# EIB-128v2.net
KiCad netlist of a schematic drawn in EAGLE
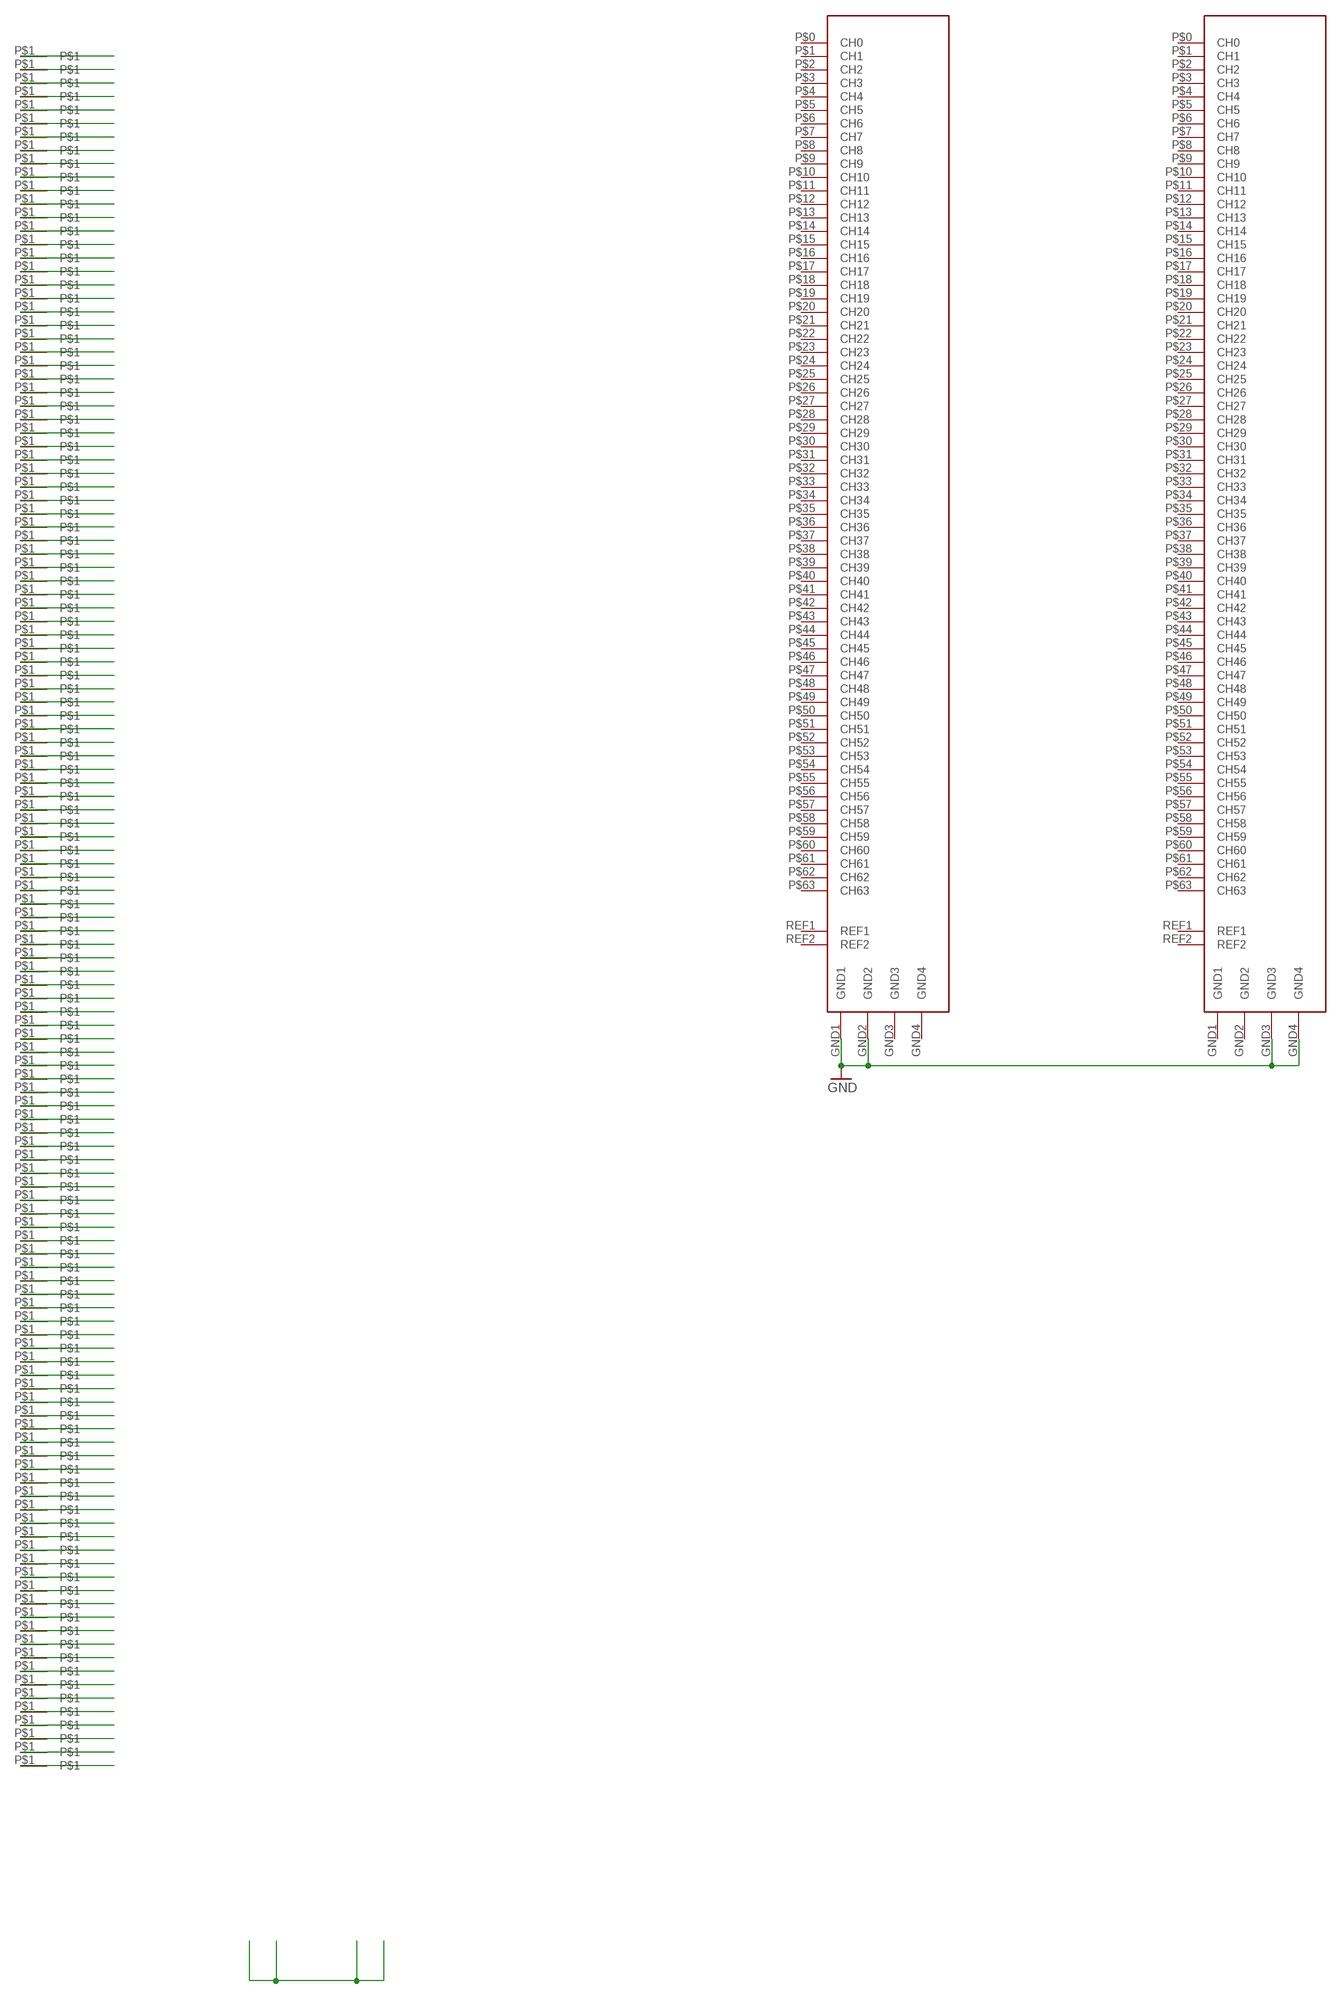
[diagram p0: schematic, sheet 1]

(export (version "E")
  (design (tool "Eeschema 10.0.6"))
  (components
    (comp (ref "H$0")
      (value "TARRAYSHUTTLEHOLE")
      (footprint "eagle-import:TARRAYSHUTTLEHOLE")
      (libsource (lib "eagle-import") (part "TARRAYSHUTTLEHOLE"))
    )
    (comp (ref "H$1")
      (value "TARRAYSHUTTLEHOLE")
      (footprint "eagle-import:TARRAYSHUTTLEHOLE")
      (libsource (lib "eagle-import") (part "TARRAYSHUTTLEHOLE"))
    )
    (comp (ref "H$2")
      (value "TARRAYSHUTTLEHOLE")
      (footprint "eagle-import:TARRAYSHUTTLEHOLE")
      (libsource (lib "eagle-import") (part "TARRAYSHUTTLEHOLE"))
    )
    (comp (ref "H$3")
      (value "TARRAYSHUTTLEHOLE")
      (footprint "eagle-import:TARRAYSHUTTLEHOLE")
      (libsource (lib "eagle-import") (part "TARRAYSHUTTLEHOLE"))
    )
    (comp (ref "H$4")
      (value "TARRAYSHUTTLEHOLE")
      (footprint "eagle-import:TARRAYSHUTTLEHOLE")
      (libsource (lib "eagle-import") (part "TARRAYSHUTTLEHOLE"))
    )
    (comp (ref "H$5")
      (value "TARRAYSHUTTLEHOLE")
      (footprint "eagle-import:TARRAYSHUTTLEHOLE")
      (libsource (lib "eagle-import") (part "TARRAYSHUTTLEHOLE"))
    )
    (comp (ref "H$6")
      (value "TARRAYSHUTTLEHOLE")
      (footprint "eagle-import:TARRAYSHUTTLEHOLE")
      (libsource (lib "eagle-import") (part "TARRAYSHUTTLEHOLE"))
    )
    (comp (ref "H$7")
      (value "TARRAYSHUTTLEHOLE")
      (footprint "eagle-import:TARRAYSHUTTLEHOLE")
      (libsource (lib "eagle-import") (part "TARRAYSHUTTLEHOLE"))
    )
    (comp (ref "H$8")
      (value "TARRAYSHUTTLEHOLE")
      (footprint "eagle-import:TARRAYSHUTTLEHOLE")
      (libsource (lib "eagle-import") (part "TARRAYSHUTTLEHOLE"))
    )
    (comp (ref "H$9")
      (value "TARRAYSHUTTLEHOLE")
      (footprint "eagle-import:TARRAYSHUTTLEHOLE")
      (libsource (lib "eagle-import") (part "TARRAYSHUTTLEHOLE"))
    )
    (comp (ref "H$10")
      (value "TARRAYSHUTTLEHOLE")
      (footprint "eagle-import:TARRAYSHUTTLEHOLE")
      (libsource (lib "eagle-import") (part "TARRAYSHUTTLEHOLE"))
    )
    (comp (ref "H$11")
      (value "TARRAYSHUTTLEHOLE")
      (footprint "eagle-import:TARRAYSHUTTLEHOLE")
      (libsource (lib "eagle-import") (part "TARRAYSHUTTLEHOLE"))
    )
    (comp (ref "H$12")
      (value "TARRAYSHUTTLEHOLE")
      (footprint "eagle-import:TARRAYSHUTTLEHOLE")
      (libsource (lib "eagle-import") (part "TARRAYSHUTTLEHOLE"))
    )
    (comp (ref "H$13")
      (value "TARRAYSHUTTLEHOLE")
      (footprint "eagle-import:TARRAYSHUTTLEHOLE")
      (libsource (lib "eagle-import") (part "TARRAYSHUTTLEHOLE"))
    )
    (comp (ref "H$14")
      (value "TARRAYSHUTTLEHOLE")
      (footprint "eagle-import:TARRAYSHUTTLEHOLE")
      (libsource (lib "eagle-import") (part "TARRAYSHUTTLEHOLE"))
    )
    (comp (ref "H$15")
      (value "TARRAYSHUTTLEHOLE")
      (footprint "eagle-import:TARRAYSHUTTLEHOLE")
      (libsource (lib "eagle-import") (part "TARRAYSHUTTLEHOLE"))
    )
    (comp (ref "H$16")
      (value "TARRAYSHUTTLEHOLE")
      (footprint "eagle-import:TARRAYSHUTTLEHOLE")
      (libsource (lib "eagle-import") (part "TARRAYSHUTTLEHOLE"))
    )
    (comp (ref "H$17")
      (value "TARRAYSHUTTLEHOLE")
      (footprint "eagle-import:TARRAYSHUTTLEHOLE")
      (libsource (lib "eagle-import") (part "TARRAYSHUTTLEHOLE"))
    )
    (comp (ref "H$18")
      (value "TARRAYSHUTTLEHOLE")
      (footprint "eagle-import:TARRAYSHUTTLEHOLE")
      (libsource (lib "eagle-import") (part "TARRAYSHUTTLEHOLE"))
    )
    (comp (ref "H$19")
      (value "TARRAYSHUTTLEHOLE")
      (footprint "eagle-import:TARRAYSHUTTLEHOLE")
      (libsource (lib "eagle-import") (part "TARRAYSHUTTLEHOLE"))
    )
    (comp (ref "H$20")
      (value "TARRAYSHUTTLEHOLE")
      (footprint "eagle-import:TARRAYSHUTTLEHOLE")
      (libsource (lib "eagle-import") (part "TARRAYSHUTTLEHOLE"))
    )
    (comp (ref "H$21")
      (value "TARRAYSHUTTLEHOLE")
      (footprint "eagle-import:TARRAYSHUTTLEHOLE")
      (libsource (lib "eagle-import") (part "TARRAYSHUTTLEHOLE"))
    )
    (comp (ref "H$22")
      (value "TARRAYSHUTTLEHOLE")
      (footprint "eagle-import:TARRAYSHUTTLEHOLE")
      (libsource (lib "eagle-import") (part "TARRAYSHUTTLEHOLE"))
    )
    (comp (ref "H$23")
      (value "TARRAYSHUTTLEHOLE")
      (footprint "eagle-import:TARRAYSHUTTLEHOLE")
      (libsource (lib "eagle-import") (part "TARRAYSHUTTLEHOLE"))
    )
    (comp (ref "H$24")
      (value "TARRAYSHUTTLEHOLE")
      (footprint "eagle-import:TARRAYSHUTTLEHOLE")
      (libsource (lib "eagle-import") (part "TARRAYSHUTTLEHOLE"))
    )
    (comp (ref "H$25")
      (value "TARRAYSHUTTLEHOLE")
      (footprint "eagle-import:TARRAYSHUTTLEHOLE")
      (libsource (lib "eagle-import") (part "TARRAYSHUTTLEHOLE"))
    )
    (comp (ref "H$26")
      (value "TARRAYSHUTTLEHOLE")
      (footprint "eagle-import:TARRAYSHUTTLEHOLE")
      (libsource (lib "eagle-import") (part "TARRAYSHUTTLEHOLE"))
    )
    (comp (ref "H$27")
      (value "TARRAYSHUTTLEHOLE")
      (footprint "eagle-import:TARRAYSHUTTLEHOLE")
      (libsource (lib "eagle-import") (part "TARRAYSHUTTLEHOLE"))
    )
    (comp (ref "H$28")
      (value "TARRAYSHUTTLEHOLE")
      (footprint "eagle-import:TARRAYSHUTTLEHOLE")
      (libsource (lib "eagle-import") (part "TARRAYSHUTTLEHOLE"))
    )
    (comp (ref "H$29")
      (value "TARRAYSHUTTLEHOLE")
      (footprint "eagle-import:TARRAYSHUTTLEHOLE")
      (libsource (lib "eagle-import") (part "TARRAYSHUTTLEHOLE"))
    )
    (comp (ref "H$30")
      (value "TARRAYSHUTTLEHOLE")
      (footprint "eagle-import:TARRAYSHUTTLEHOLE")
      (libsource (lib "eagle-import") (part "TARRAYSHUTTLEHOLE"))
    )
    (comp (ref "H$31")
      (value "TARRAYSHUTTLEHOLE")
      (footprint "eagle-import:TARRAYSHUTTLEHOLE")
      (libsource (lib "eagle-import") (part "TARRAYSHUTTLEHOLE"))
    )
    (comp (ref "H$32")
      (value "TARRAYSHUTTLEHOLE")
      (footprint "eagle-import:TARRAYSHUTTLEHOLE")
      (libsource (lib "eagle-import") (part "TARRAYSHUTTLEHOLE"))
    )
    (comp (ref "H$33")
      (value "TARRAYSHUTTLEHOLE")
      (footprint "eagle-import:TARRAYSHUTTLEHOLE")
      (libsource (lib "eagle-import") (part "TARRAYSHUTTLEHOLE"))
    )
    (comp (ref "H$34")
      (value "TARRAYSHUTTLEHOLE")
      (footprint "eagle-import:TARRAYSHUTTLEHOLE")
      (libsource (lib "eagle-import") (part "TARRAYSHUTTLEHOLE"))
    )
    (comp (ref "H$35")
      (value "TARRAYSHUTTLEHOLE")
      (footprint "eagle-import:TARRAYSHUTTLEHOLE")
      (libsource (lib "eagle-import") (part "TARRAYSHUTTLEHOLE"))
    )
    (comp (ref "H$36")
      (value "TARRAYSHUTTLEHOLE")
      (footprint "eagle-import:TARRAYSHUTTLEHOLE")
      (libsource (lib "eagle-import") (part "TARRAYSHUTTLEHOLE"))
    )
    (comp (ref "H$37")
      (value "TARRAYSHUTTLEHOLE")
      (footprint "eagle-import:TARRAYSHUTTLEHOLE")
      (libsource (lib "eagle-import") (part "TARRAYSHUTTLEHOLE"))
    )
    (comp (ref "H$38")
      (value "TARRAYSHUTTLEHOLE")
      (footprint "eagle-import:TARRAYSHUTTLEHOLE")
      (libsource (lib "eagle-import") (part "TARRAYSHUTTLEHOLE"))
    )
    (comp (ref "H$39")
      (value "TARRAYSHUTTLEHOLE")
      (footprint "eagle-import:TARRAYSHUTTLEHOLE")
      (libsource (lib "eagle-import") (part "TARRAYSHUTTLEHOLE"))
    )
    (comp (ref "H$40")
      (value "TARRAYSHUTTLEHOLE")
      (footprint "eagle-import:TARRAYSHUTTLEHOLE")
      (libsource (lib "eagle-import") (part "TARRAYSHUTTLEHOLE"))
    )
    (comp (ref "H$41")
      (value "TARRAYSHUTTLEHOLE")
      (footprint "eagle-import:TARRAYSHUTTLEHOLE")
      (libsource (lib "eagle-import") (part "TARRAYSHUTTLEHOLE"))
    )
    (comp (ref "H$42")
      (value "TARRAYSHUTTLEHOLE")
      (footprint "eagle-import:TARRAYSHUTTLEHOLE")
      (libsource (lib "eagle-import") (part "TARRAYSHUTTLEHOLE"))
    )
    (comp (ref "H$43")
      (value "TARRAYSHUTTLEHOLE")
      (footprint "eagle-import:TARRAYSHUTTLEHOLE")
      (libsource (lib "eagle-import") (part "TARRAYSHUTTLEHOLE"))
    )
    (comp (ref "H$44")
      (value "TARRAYSHUTTLEHOLE")
      (footprint "eagle-import:TARRAYSHUTTLEHOLE")
      (libsource (lib "eagle-import") (part "TARRAYSHUTTLEHOLE"))
    )
    (comp (ref "H$45")
      (value "TARRAYSHUTTLEHOLE")
      (footprint "eagle-import:TARRAYSHUTTLEHOLE")
      (libsource (lib "eagle-import") (part "TARRAYSHUTTLEHOLE"))
    )
    (comp (ref "H$46")
      (value "TARRAYSHUTTLEHOLE")
      (footprint "eagle-import:TARRAYSHUTTLEHOLE")
      (libsource (lib "eagle-import") (part "TARRAYSHUTTLEHOLE"))
    )
    (comp (ref "H$47")
      (value "TARRAYSHUTTLEHOLE")
      (footprint "eagle-import:TARRAYSHUTTLEHOLE")
      (libsource (lib "eagle-import") (part "TARRAYSHUTTLEHOLE"))
    )
    (comp (ref "H$48")
      (value "TARRAYSHUTTLEHOLE")
      (footprint "eagle-import:TARRAYSHUTTLEHOLE")
      (libsource (lib "eagle-import") (part "TARRAYSHUTTLEHOLE"))
    )
    (comp (ref "H$49")
      (value "TARRAYSHUTTLEHOLE")
      (footprint "eagle-import:TARRAYSHUTTLEHOLE")
      (libsource (lib "eagle-import") (part "TARRAYSHUTTLEHOLE"))
    )
    (comp (ref "H$50")
      (value "TARRAYSHUTTLEHOLE")
      (footprint "eagle-import:TARRAYSHUTTLEHOLE")
      (libsource (lib "eagle-import") (part "TARRAYSHUTTLEHOLE"))
    )
    (comp (ref "H$51")
      (value "TARRAYSHUTTLEHOLE")
      (footprint "eagle-import:TARRAYSHUTTLEHOLE")
      (libsource (lib "eagle-import") (part "TARRAYSHUTTLEHOLE"))
    )
    (comp (ref "H$52")
      (value "TARRAYSHUTTLEHOLE")
      (footprint "eagle-import:TARRAYSHUTTLEHOLE")
      (libsource (lib "eagle-import") (part "TARRAYSHUTTLEHOLE"))
    )
    (comp (ref "H$53")
      (value "TARRAYSHUTTLEHOLE")
      (footprint "eagle-import:TARRAYSHUTTLEHOLE")
      (libsource (lib "eagle-import") (part "TARRAYSHUTTLEHOLE"))
    )
    (comp (ref "H$54")
      (value "TARRAYSHUTTLEHOLE")
      (footprint "eagle-import:TARRAYSHUTTLEHOLE")
      (libsource (lib "eagle-import") (part "TARRAYSHUTTLEHOLE"))
    )
    (comp (ref "H$55")
      (value "TARRAYSHUTTLEHOLE")
      (footprint "eagle-import:TARRAYSHUTTLEHOLE")
      (libsource (lib "eagle-import") (part "TARRAYSHUTTLEHOLE"))
    )
    (comp (ref "H$56")
      (value "TARRAYSHUTTLEHOLE")
      (footprint "eagle-import:TARRAYSHUTTLEHOLE")
      (libsource (lib "eagle-import") (part "TARRAYSHUTTLEHOLE"))
    )
    (comp (ref "H$57")
      (value "TARRAYSHUTTLEHOLE")
      (footprint "eagle-import:TARRAYSHUTTLEHOLE")
      (libsource (lib "eagle-import") (part "TARRAYSHUTTLEHOLE"))
    )
    (comp (ref "H$58")
      (value "TARRAYSHUTTLEHOLE")
      (footprint "eagle-import:TARRAYSHUTTLEHOLE")
      (libsource (lib "eagle-import") (part "TARRAYSHUTTLEHOLE"))
    )
    (comp (ref "H$59")
      (value "TARRAYSHUTTLEHOLE")
      (footprint "eagle-import:TARRAYSHUTTLEHOLE")
      (libsource (lib "eagle-import") (part "TARRAYSHUTTLEHOLE"))
    )
    (comp (ref "H$60")
      (value "TARRAYSHUTTLEHOLE")
      (footprint "eagle-import:TARRAYSHUTTLEHOLE")
      (libsource (lib "eagle-import") (part "TARRAYSHUTTLEHOLE"))
    )
    (comp (ref "H$61")
      (value "TARRAYSHUTTLEHOLE")
      (footprint "eagle-import:TARRAYSHUTTLEHOLE")
      (libsource (lib "eagle-import") (part "TARRAYSHUTTLEHOLE"))
    )
    (comp (ref "H$62")
      (value "TARRAYSHUTTLEHOLE")
      (footprint "eagle-import:TARRAYSHUTTLEHOLE")
      (libsource (lib "eagle-import") (part "TARRAYSHUTTLEHOLE"))
    )
    (comp (ref "H$63")
      (value "TARRAYSHUTTLEHOLE")
      (footprint "eagle-import:TARRAYSHUTTLEHOLE")
      (libsource (lib "eagle-import") (part "TARRAYSHUTTLEHOLE"))
    )
    (comp (ref "H$64")
      (value "TARRAYSHUTTLEHOLE")
      (footprint "eagle-import:TARRAYSHUTTLEHOLE")
      (libsource (lib "eagle-import") (part "TARRAYSHUTTLEHOLE"))
    )
    (comp (ref "H$65")
      (value "TARRAYSHUTTLEHOLE")
      (footprint "eagle-import:TARRAYSHUTTLEHOLE")
      (libsource (lib "eagle-import") (part "TARRAYSHUTTLEHOLE"))
    )
    (comp (ref "H$66")
      (value "TARRAYSHUTTLEHOLE")
      (footprint "eagle-import:TARRAYSHUTTLEHOLE")
      (libsource (lib "eagle-import") (part "TARRAYSHUTTLEHOLE"))
    )
    (comp (ref "H$67")
      (value "TARRAYSHUTTLEHOLE")
      (footprint "eagle-import:TARRAYSHUTTLEHOLE")
      (libsource (lib "eagle-import") (part "TARRAYSHUTTLEHOLE"))
    )
    (comp (ref "H$68")
      (value "TARRAYSHUTTLEHOLE")
      (footprint "eagle-import:TARRAYSHUTTLEHOLE")
      (libsource (lib "eagle-import") (part "TARRAYSHUTTLEHOLE"))
    )
    (comp (ref "H$69")
      (value "TARRAYSHUTTLEHOLE")
      (footprint "eagle-import:TARRAYSHUTTLEHOLE")
      (libsource (lib "eagle-import") (part "TARRAYSHUTTLEHOLE"))
    )
    (comp (ref "H$70")
      (value "TARRAYSHUTTLEHOLE")
      (footprint "eagle-import:TARRAYSHUTTLEHOLE")
      (libsource (lib "eagle-import") (part "TARRAYSHUTTLEHOLE"))
    )
    (comp (ref "H$71")
      (value "TARRAYSHUTTLEHOLE")
      (footprint "eagle-import:TARRAYSHUTTLEHOLE")
      (libsource (lib "eagle-import") (part "TARRAYSHUTTLEHOLE"))
    )
    (comp (ref "H$72")
      (value "TARRAYSHUTTLEHOLE")
      (footprint "eagle-import:TARRAYSHUTTLEHOLE")
      (libsource (lib "eagle-import") (part "TARRAYSHUTTLEHOLE"))
    )
    (comp (ref "H$73")
      (value "TARRAYSHUTTLEHOLE")
      (footprint "eagle-import:TARRAYSHUTTLEHOLE")
      (libsource (lib "eagle-import") (part "TARRAYSHUTTLEHOLE"))
    )
    (comp (ref "H$74")
      (value "TARRAYSHUTTLEHOLE")
      (footprint "eagle-import:TARRAYSHUTTLEHOLE")
      (libsource (lib "eagle-import") (part "TARRAYSHUTTLEHOLE"))
    )
    (comp (ref "H$75")
      (value "TARRAYSHUTTLEHOLE")
      (footprint "eagle-import:TARRAYSHUTTLEHOLE")
      (libsource (lib "eagle-import") (part "TARRAYSHUTTLEHOLE"))
    )
    (comp (ref "H$76")
      (value "TARRAYSHUTTLEHOLE")
      (footprint "eagle-import:TARRAYSHUTTLEHOLE")
      (libsource (lib "eagle-import") (part "TARRAYSHUTTLEHOLE"))
    )
    (comp (ref "H$77")
      (value "TARRAYSHUTTLEHOLE")
      (footprint "eagle-import:TARRAYSHUTTLEHOLE")
      (libsource (lib "eagle-import") (part "TARRAYSHUTTLEHOLE"))
    )
    (comp (ref "H$78")
      (value "TARRAYSHUTTLEHOLE")
      (footprint "eagle-import:TARRAYSHUTTLEHOLE")
      (libsource (lib "eagle-import") (part "TARRAYSHUTTLEHOLE"))
    )
    (comp (ref "H$79")
      (value "TARRAYSHUTTLEHOLE")
      (footprint "eagle-import:TARRAYSHUTTLEHOLE")
      (libsource (lib "eagle-import") (part "TARRAYSHUTTLEHOLE"))
    )
    (comp (ref "H$80")
      (value "TARRAYSHUTTLEHOLE")
      (footprint "eagle-import:TARRAYSHUTTLEHOLE")
      (libsource (lib "eagle-import") (part "TARRAYSHUTTLEHOLE"))
    )
    (comp (ref "H$81")
      (value "TARRAYSHUTTLEHOLE")
      (footprint "eagle-import:TARRAYSHUTTLEHOLE")
      (libsource (lib "eagle-import") (part "TARRAYSHUTTLEHOLE"))
    )
    (comp (ref "H$82")
      (value "TARRAYSHUTTLEHOLE")
      (footprint "eagle-import:TARRAYSHUTTLEHOLE")
      (libsource (lib "eagle-import") (part "TARRAYSHUTTLEHOLE"))
    )
    (comp (ref "H$83")
      (value "TARRAYSHUTTLEHOLE")
      (footprint "eagle-import:TARRAYSHUTTLEHOLE")
      (libsource (lib "eagle-import") (part "TARRAYSHUTTLEHOLE"))
    )
    (comp (ref "H$84")
      (value "TARRAYSHUTTLEHOLE")
      (footprint "eagle-import:TARRAYSHUTTLEHOLE")
      (libsource (lib "eagle-import") (part "TARRAYSHUTTLEHOLE"))
    )
    (comp (ref "H$85")
      (value "TARRAYSHUTTLEHOLE")
      (footprint "eagle-import:TARRAYSHUTTLEHOLE")
      (libsource (lib "eagle-import") (part "TARRAYSHUTTLEHOLE"))
    )
    (comp (ref "H$86")
      (value "TARRAYSHUTTLEHOLE")
      (footprint "eagle-import:TARRAYSHUTTLEHOLE")
      (libsource (lib "eagle-import") (part "TARRAYSHUTTLEHOLE"))
    )
    (comp (ref "H$87")
      (value "TARRAYSHUTTLEHOLE")
      (footprint "eagle-import:TARRAYSHUTTLEHOLE")
      (libsource (lib "eagle-import") (part "TARRAYSHUTTLEHOLE"))
    )
    (comp (ref "H$88")
      (value "TARRAYSHUTTLEHOLE")
      (footprint "eagle-import:TARRAYSHUTTLEHOLE")
      (libsource (lib "eagle-import") (part "TARRAYSHUTTLEHOLE"))
    )
    (comp (ref "H$89")
      (value "TARRAYSHUTTLEHOLE")
      (footprint "eagle-import:TARRAYSHUTTLEHOLE")
      (libsource (lib "eagle-import") (part "TARRAYSHUTTLEHOLE"))
    )
    (comp (ref "H$90")
      (value "TARRAYSHUTTLEHOLE")
      (footprint "eagle-import:TARRAYSHUTTLEHOLE")
      (libsource (lib "eagle-import") (part "TARRAYSHUTTLEHOLE"))
    )
    (comp (ref "H$91")
      (value "TARRAYSHUTTLEHOLE")
      (footprint "eagle-import:TARRAYSHUTTLEHOLE")
      (libsource (lib "eagle-import") (part "TARRAYSHUTTLEHOLE"))
    )
    (comp (ref "H$92")
      (value "TARRAYSHUTTLEHOLE")
      (footprint "eagle-import:TARRAYSHUTTLEHOLE")
      (libsource (lib "eagle-import") (part "TARRAYSHUTTLEHOLE"))
    )
    (comp (ref "H$93")
      (value "TARRAYSHUTTLEHOLE")
      (footprint "eagle-import:TARRAYSHUTTLEHOLE")
      (libsource (lib "eagle-import") (part "TARRAYSHUTTLEHOLE"))
    )
    (comp (ref "H$94")
      (value "TARRAYSHUTTLEHOLE")
      (footprint "eagle-import:TARRAYSHUTTLEHOLE")
      (libsource (lib "eagle-import") (part "TARRAYSHUTTLEHOLE"))
    )
    (comp (ref "H$95")
      (value "TARRAYSHUTTLEHOLE")
      (footprint "eagle-import:TARRAYSHUTTLEHOLE")
      (libsource (lib "eagle-import") (part "TARRAYSHUTTLEHOLE"))
    )
    (comp (ref "H$96")
      (value "TARRAYSHUTTLEHOLE")
      (footprint "eagle-import:TARRAYSHUTTLEHOLE")
      (libsource (lib "eagle-import") (part "TARRAYSHUTTLEHOLE"))
    )
    (comp (ref "H$97")
      (value "TARRAYSHUTTLEHOLE")
      (footprint "eagle-import:TARRAYSHUTTLEHOLE")
      (libsource (lib "eagle-import") (part "TARRAYSHUTTLEHOLE"))
    )
    (comp (ref "H$98")
      (value "TARRAYSHUTTLEHOLE")
      (footprint "eagle-import:TARRAYSHUTTLEHOLE")
      (libsource (lib "eagle-import") (part "TARRAYSHUTTLEHOLE"))
    )
    (comp (ref "H$99")
      (value "TARRAYSHUTTLEHOLE")
      (footprint "eagle-import:TARRAYSHUTTLEHOLE")
      (libsource (lib "eagle-import") (part "TARRAYSHUTTLEHOLE"))
    )
    (comp (ref "H$100")
      (value "TARRAYSHUTTLEHOLE")
      (footprint "eagle-import:TARRAYSHUTTLEHOLE")
      (libsource (lib "eagle-import") (part "TARRAYSHUTTLEHOLE"))
    )
    (comp (ref "H$101")
      (value "TARRAYSHUTTLEHOLE")
      (footprint "eagle-import:TARRAYSHUTTLEHOLE")
      (libsource (lib "eagle-import") (part "TARRAYSHUTTLEHOLE"))
    )
    (comp (ref "H$102")
      (value "TARRAYSHUTTLEHOLE")
      (footprint "eagle-import:TARRAYSHUTTLEHOLE")
      (libsource (lib "eagle-import") (part "TARRAYSHUTTLEHOLE"))
    )
    (comp (ref "H$103")
      (value "TARRAYSHUTTLEHOLE")
      (footprint "eagle-import:TARRAYSHUTTLEHOLE")
      (libsource (lib "eagle-import") (part "TARRAYSHUTTLEHOLE"))
    )
    (comp (ref "H$104")
      (value "TARRAYSHUTTLEHOLE")
      (footprint "eagle-import:TARRAYSHUTTLEHOLE")
      (libsource (lib "eagle-import") (part "TARRAYSHUTTLEHOLE"))
    )
    (comp (ref "H$105")
      (value "TARRAYSHUTTLEHOLE")
      (footprint "eagle-import:TARRAYSHUTTLEHOLE")
      (libsource (lib "eagle-import") (part "TARRAYSHUTTLEHOLE"))
    )
    (comp (ref "H$106")
      (value "TARRAYSHUTTLEHOLE")
      (footprint "eagle-import:TARRAYSHUTTLEHOLE")
      (libsource (lib "eagle-import") (part "TARRAYSHUTTLEHOLE"))
    )
    (comp (ref "H$107")
      (value "TARRAYSHUTTLEHOLE")
      (footprint "eagle-import:TARRAYSHUTTLEHOLE")
      (libsource (lib "eagle-import") (part "TARRAYSHUTTLEHOLE"))
    )
    (comp (ref "H$108")
      (value "TARRAYSHUTTLEHOLE")
      (footprint "eagle-import:TARRAYSHUTTLEHOLE")
      (libsource (lib "eagle-import") (part "TARRAYSHUTTLEHOLE"))
    )
    (comp (ref "H$109")
      (value "TARRAYSHUTTLEHOLE")
      (footprint "eagle-import:TARRAYSHUTTLEHOLE")
      (libsource (lib "eagle-import") (part "TARRAYSHUTTLEHOLE"))
    )
    (comp (ref "H$110")
      (value "TARRAYSHUTTLEHOLE")
      (footprint "eagle-import:TARRAYSHUTTLEHOLE")
      (libsource (lib "eagle-import") (part "TARRAYSHUTTLEHOLE"))
    )
    (comp (ref "H$111")
      (value "TARRAYSHUTTLEHOLE")
      (footprint "eagle-import:TARRAYSHUTTLEHOLE")
      (libsource (lib "eagle-import") (part "TARRAYSHUTTLEHOLE"))
    )
    (comp (ref "H$112")
      (value "TARRAYSHUTTLEHOLE")
      (footprint "eagle-import:TARRAYSHUTTLEHOLE")
      (libsource (lib "eagle-import") (part "TARRAYSHUTTLEHOLE"))
    )
    (comp (ref "H$113")
      (value "TARRAYSHUTTLEHOLE")
      (footprint "eagle-import:TARRAYSHUTTLEHOLE")
      (libsource (lib "eagle-import") (part "TARRAYSHUTTLEHOLE"))
    )
    (comp (ref "H$114")
      (value "TARRAYSHUTTLEHOLE")
      (footprint "eagle-import:TARRAYSHUTTLEHOLE")
      (libsource (lib "eagle-import") (part "TARRAYSHUTTLEHOLE"))
    )
    (comp (ref "H$115")
      (value "TARRAYSHUTTLEHOLE")
      (footprint "eagle-import:TARRAYSHUTTLEHOLE")
      (libsource (lib "eagle-import") (part "TARRAYSHUTTLEHOLE"))
    )
    (comp (ref "H$116")
      (value "TARRAYSHUTTLEHOLE")
      (footprint "eagle-import:TARRAYSHUTTLEHOLE")
      (libsource (lib "eagle-import") (part "TARRAYSHUTTLEHOLE"))
    )
    (comp (ref "H$117")
      (value "TARRAYSHUTTLEHOLE")
      (footprint "eagle-import:TARRAYSHUTTLEHOLE")
      (libsource (lib "eagle-import") (part "TARRAYSHUTTLEHOLE"))
    )
    (comp (ref "H$118")
      (value "TARRAYSHUTTLEHOLE")
      (footprint "eagle-import:TARRAYSHUTTLEHOLE")
      (libsource (lib "eagle-import") (part "TARRAYSHUTTLEHOLE"))
    )
    (comp (ref "H$119")
      (value "TARRAYSHUTTLEHOLE")
      (footprint "eagle-import:TARRAYSHUTTLEHOLE")
      (libsource (lib "eagle-import") (part "TARRAYSHUTTLEHOLE"))
    )
    (comp (ref "H$120")
      (value "TARRAYSHUTTLEHOLE")
      (footprint "eagle-import:TARRAYSHUTTLEHOLE")
      (libsource (lib "eagle-import") (part "TARRAYSHUTTLEHOLE"))
    )
    (comp (ref "H$121")
      (value "TARRAYSHUTTLEHOLE")
      (footprint "eagle-import:TARRAYSHUTTLEHOLE")
      (libsource (lib "eagle-import") (part "TARRAYSHUTTLEHOLE"))
    )
    (comp (ref "H$122")
      (value "TARRAYSHUTTLEHOLE")
      (footprint "eagle-import:TARRAYSHUTTLEHOLE")
      (libsource (lib "eagle-import") (part "TARRAYSHUTTLEHOLE"))
    )
    (comp (ref "H$123")
      (value "TARRAYSHUTTLEHOLE")
      (footprint "eagle-import:TARRAYSHUTTLEHOLE")
      (libsource (lib "eagle-import") (part "TARRAYSHUTTLEHOLE"))
    )
    (comp (ref "H$124")
      (value "TARRAYSHUTTLEHOLE")
      (footprint "eagle-import:TARRAYSHUTTLEHOLE")
      (libsource (lib "eagle-import") (part "TARRAYSHUTTLEHOLE"))
    )
    (comp (ref "H$125")
      (value "TARRAYSHUTTLEHOLE")
      (footprint "eagle-import:TARRAYSHUTTLEHOLE")
      (libsource (lib "eagle-import") (part "TARRAYSHUTTLEHOLE"))
    )
    (comp (ref "H$126")
      (value "TARRAYSHUTTLEHOLE")
      (footprint "eagle-import:TARRAYSHUTTLEHOLE")
      (libsource (lib "eagle-import") (part "TARRAYSHUTTLEHOLE"))
    )
    (comp (ref "H$127")
      (value "TARRAYSHUTTLEHOLE")
      (footprint "eagle-import:TARRAYSHUTTLEHOLE")
      (libsource (lib "eagle-import") (part "TARRAYSHUTTLEHOLE"))
    )
    (comp (ref "U$1")
      (value "DF40C-70DP")
      (footprint "eagle-import:DF40C-70DP")
      (libsource (lib "eagle-import") (part "DF40C-70DP"))
    )
    (comp (ref "U$2")
      (value "DF40C-70DP")
      (footprint "eagle-import:DF40C-70DP")
      (libsource (lib "eagle-import") (part "DF40C-70DP"))
    )
  )
  (nets
    (net (code "1") (name "GND") (class "Default")
      (node (ref "U$1") (pin "GND1") (pinfunction "GND1_GND1") (pintype "bidirectional"))
      (node (ref "U$1") (pin "GND2") (pinfunction "GND2_GND2") (pintype "bidirectional"))
      (node (ref "U$2") (pin "GND3") (pinfunction "GND3_GND3") (pintype "bidirectional"))
      (node (ref "U$2") (pin "GND4") (pinfunction "GND4_GND4") (pintype "bidirectional"))
    )
    (net (code "2") (name "unconnected-(H$0-PadP$1)") (class "Default")
      (node (ref "H$0") (pin "P$1") (pinfunction "P$1_P$1") (pintype "bidirectional"))
    )
    (net (code "3") (name "unconnected-(H$1-PadP$1)") (class "Default")
      (node (ref "H$1") (pin "P$1") (pinfunction "P$1_P$1") (pintype "bidirectional"))
    )
    (net (code "4") (name "unconnected-(H$2-PadP$1)") (class "Default")
      (node (ref "H$2") (pin "P$1") (pinfunction "P$1_P$1") (pintype "bidirectional"))
    )
    (net (code "5") (name "unconnected-(H$3-PadP$1)") (class "Default")
      (node (ref "H$3") (pin "P$1") (pinfunction "P$1_P$1") (pintype "bidirectional"))
    )
    (net (code "6") (name "unconnected-(H$4-PadP$1)") (class "Default")
      (node (ref "H$4") (pin "P$1") (pinfunction "P$1_P$1") (pintype "bidirectional"))
    )
    (net (code "7") (name "unconnected-(H$5-PadP$1)") (class "Default")
      (node (ref "H$5") (pin "P$1") (pinfunction "P$1_P$1") (pintype "bidirectional"))
    )
    (net (code "8") (name "unconnected-(H$6-PadP$1)") (class "Default")
      (node (ref "H$6") (pin "P$1") (pinfunction "P$1_P$1") (pintype "bidirectional"))
    )
    (net (code "9") (name "unconnected-(H$7-PadP$1)") (class "Default")
      (node (ref "H$7") (pin "P$1") (pinfunction "P$1_P$1") (pintype "bidirectional"))
    )
    (net (code "10") (name "unconnected-(H$8-PadP$1)") (class "Default")
      (node (ref "H$8") (pin "P$1") (pinfunction "P$1_P$1") (pintype "bidirectional"))
    )
    (net (code "11") (name "unconnected-(H$9-PadP$1)") (class "Default")
      (node (ref "H$9") (pin "P$1") (pinfunction "P$1_P$1") (pintype "bidirectional"))
    )
    (net (code "12") (name "unconnected-(H$10-PadP$1)") (class "Default")
      (node (ref "H$10") (pin "P$1") (pinfunction "P$1_P$1") (pintype "bidirectional"))
    )
    (net (code "13") (name "unconnected-(H$11-PadP$1)") (class "Default")
      (node (ref "H$11") (pin "P$1") (pinfunction "P$1_P$1") (pintype "bidirectional"))
    )
    (net (code "14") (name "unconnected-(H$12-PadP$1)") (class "Default")
      (node (ref "H$12") (pin "P$1") (pinfunction "P$1_P$1") (pintype "bidirectional"))
    )
    (net (code "15") (name "unconnected-(H$13-PadP$1)") (class "Default")
      (node (ref "H$13") (pin "P$1") (pinfunction "P$1_P$1") (pintype "bidirectional"))
    )
    (net (code "16") (name "unconnected-(H$14-PadP$1)") (class "Default")
      (node (ref "H$14") (pin "P$1") (pinfunction "P$1_P$1") (pintype "bidirectional"))
    )
    (net (code "17") (name "unconnected-(H$15-PadP$1)") (class "Default")
      (node (ref "H$15") (pin "P$1") (pinfunction "P$1_P$1") (pintype "bidirectional"))
    )
    (net (code "18") (name "unconnected-(H$16-PadP$1)") (class "Default")
      (node (ref "H$16") (pin "P$1") (pinfunction "P$1_P$1") (pintype "bidirectional"))
    )
    (net (code "19") (name "unconnected-(H$17-PadP$1)") (class "Default")
      (node (ref "H$17") (pin "P$1") (pinfunction "P$1_P$1") (pintype "bidirectional"))
    )
    (net (code "20") (name "unconnected-(H$18-PadP$1)") (class "Default")
      (node (ref "H$18") (pin "P$1") (pinfunction "P$1_P$1") (pintype "bidirectional"))
    )
    (net (code "21") (name "unconnected-(H$19-PadP$1)") (class "Default")
      (node (ref "H$19") (pin "P$1") (pinfunction "P$1_P$1") (pintype "bidirectional"))
    )
    (net (code "22") (name "unconnected-(H$20-PadP$1)") (class "Default")
      (node (ref "H$20") (pin "P$1") (pinfunction "P$1_P$1") (pintype "bidirectional"))
    )
    (net (code "23") (name "unconnected-(H$21-PadP$1)") (class "Default")
      (node (ref "H$21") (pin "P$1") (pinfunction "P$1_P$1") (pintype "bidirectional"))
    )
    (net (code "24") (name "unconnected-(H$22-PadP$1)") (class "Default")
      (node (ref "H$22") (pin "P$1") (pinfunction "P$1_P$1") (pintype "bidirectional"))
    )
    (net (code "25") (name "unconnected-(H$23-PadP$1)") (class "Default")
      (node (ref "H$23") (pin "P$1") (pinfunction "P$1_P$1") (pintype "bidirectional"))
    )
    (net (code "26") (name "unconnected-(H$24-PadP$1)") (class "Default")
      (node (ref "H$24") (pin "P$1") (pinfunction "P$1_P$1") (pintype "bidirectional"))
    )
    (net (code "27") (name "unconnected-(H$25-PadP$1)") (class "Default")
      (node (ref "H$25") (pin "P$1") (pinfunction "P$1_P$1") (pintype "bidirectional"))
    )
    (net (code "28") (name "unconnected-(H$26-PadP$1)") (class "Default")
      (node (ref "H$26") (pin "P$1") (pinfunction "P$1_P$1") (pintype "bidirectional"))
    )
    (net (code "29") (name "unconnected-(H$27-PadP$1)") (class "Default")
      (node (ref "H$27") (pin "P$1") (pinfunction "P$1_P$1") (pintype "bidirectional"))
    )
    (net (code "30") (name "unconnected-(H$28-PadP$1)") (class "Default")
      (node (ref "H$28") (pin "P$1") (pinfunction "P$1_P$1") (pintype "bidirectional"))
    )
    (net (code "31") (name "unconnected-(H$29-PadP$1)") (class "Default")
      (node (ref "H$29") (pin "P$1") (pinfunction "P$1_P$1") (pintype "bidirectional"))
    )
    (net (code "32") (name "unconnected-(H$30-PadP$1)") (class "Default")
      (node (ref "H$30") (pin "P$1") (pinfunction "P$1_P$1") (pintype "bidirectional"))
    )
    (net (code "33") (name "unconnected-(H$31-PadP$1)") (class "Default")
      (node (ref "H$31") (pin "P$1") (pinfunction "P$1_P$1") (pintype "bidirectional"))
    )
    (net (code "34") (name "unconnected-(H$32-PadP$1)") (class "Default")
      (node (ref "H$32") (pin "P$1") (pinfunction "P$1_P$1") (pintype "bidirectional"))
    )
    (net (code "35") (name "unconnected-(H$33-PadP$1)") (class "Default")
      (node (ref "H$33") (pin "P$1") (pinfunction "P$1_P$1") (pintype "bidirectional"))
    )
    (net (code "36") (name "unconnected-(H$34-PadP$1)") (class "Default")
      (node (ref "H$34") (pin "P$1") (pinfunction "P$1_P$1") (pintype "bidirectional"))
    )
    (net (code "37") (name "unconnected-(H$35-PadP$1)") (class "Default")
      (node (ref "H$35") (pin "P$1") (pinfunction "P$1_P$1") (pintype "bidirectional"))
    )
    (net (code "38") (name "unconnected-(H$36-PadP$1)") (class "Default")
      (node (ref "H$36") (pin "P$1") (pinfunction "P$1_P$1") (pintype "bidirectional"))
    )
    (net (code "39") (name "unconnected-(H$37-PadP$1)") (class "Default")
      (node (ref "H$37") (pin "P$1") (pinfunction "P$1_P$1") (pintype "bidirectional"))
    )
    (net (code "40") (name "unconnected-(H$38-PadP$1)") (class "Default")
      (node (ref "H$38") (pin "P$1") (pinfunction "P$1_P$1") (pintype "bidirectional"))
    )
    (net (code "41") (name "unconnected-(H$39-PadP$1)") (class "Default")
      (node (ref "H$39") (pin "P$1") (pinfunction "P$1_P$1") (pintype "bidirectional"))
    )
    (net (code "42") (name "unconnected-(H$40-PadP$1)") (class "Default")
      (node (ref "H$40") (pin "P$1") (pinfunction "P$1_P$1") (pintype "bidirectional"))
    )
    (net (code "43") (name "unconnected-(H$41-PadP$1)") (class "Default")
      (node (ref "H$41") (pin "P$1") (pinfunction "P$1_P$1") (pintype "bidirectional"))
    )
    (net (code "44") (name "unconnected-(H$42-PadP$1)") (class "Default")
      (node (ref "H$42") (pin "P$1") (pinfunction "P$1_P$1") (pintype "bidirectional"))
    )
    (net (code "45") (name "unconnected-(H$43-PadP$1)") (class "Default")
      (node (ref "H$43") (pin "P$1") (pinfunction "P$1_P$1") (pintype "bidirectional"))
    )
    (net (code "46") (name "unconnected-(H$44-PadP$1)") (class "Default")
      (node (ref "H$44") (pin "P$1") (pinfunction "P$1_P$1") (pintype "bidirectional"))
    )
    (net (code "47") (name "unconnected-(H$45-PadP$1)") (class "Default")
      (node (ref "H$45") (pin "P$1") (pinfunction "P$1_P$1") (pintype "bidirectional"))
    )
    (net (code "48") (name "unconnected-(H$46-PadP$1)") (class "Default")
      (node (ref "H$46") (pin "P$1") (pinfunction "P$1_P$1") (pintype "bidirectional"))
    )
    (net (code "49") (name "unconnected-(H$47-PadP$1)") (class "Default")
      (node (ref "H$47") (pin "P$1") (pinfunction "P$1_P$1") (pintype "bidirectional"))
    )
    (net (code "50") (name "unconnected-(H$48-PadP$1)") (class "Default")
      (node (ref "H$48") (pin "P$1") (pinfunction "P$1_P$1") (pintype "bidirectional"))
    )
    (net (code "51") (name "unconnected-(H$49-PadP$1)") (class "Default")
      (node (ref "H$49") (pin "P$1") (pinfunction "P$1_P$1") (pintype "bidirectional"))
    )
    (net (code "52") (name "unconnected-(H$50-PadP$1)") (class "Default")
      (node (ref "H$50") (pin "P$1") (pinfunction "P$1_P$1") (pintype "bidirectional"))
    )
    (net (code "53") (name "unconnected-(H$51-PadP$1)") (class "Default")
      (node (ref "H$51") (pin "P$1") (pinfunction "P$1_P$1") (pintype "bidirectional"))
    )
    (net (code "54") (name "unconnected-(H$52-PadP$1)") (class "Default")
      (node (ref "H$52") (pin "P$1") (pinfunction "P$1_P$1") (pintype "bidirectional"))
    )
    (net (code "55") (name "unconnected-(H$53-PadP$1)") (class "Default")
      (node (ref "H$53") (pin "P$1") (pinfunction "P$1_P$1") (pintype "bidirectional"))
    )
    (net (code "56") (name "unconnected-(H$54-PadP$1)") (class "Default")
      (node (ref "H$54") (pin "P$1") (pinfunction "P$1_P$1") (pintype "bidirectional"))
    )
    (net (code "57") (name "unconnected-(H$55-PadP$1)") (class "Default")
      (node (ref "H$55") (pin "P$1") (pinfunction "P$1_P$1") (pintype "bidirectional"))
    )
    (net (code "58") (name "unconnected-(H$56-PadP$1)") (class "Default")
      (node (ref "H$56") (pin "P$1") (pinfunction "P$1_P$1") (pintype "bidirectional"))
    )
    (net (code "59") (name "unconnected-(H$57-PadP$1)") (class "Default")
      (node (ref "H$57") (pin "P$1") (pinfunction "P$1_P$1") (pintype "bidirectional"))
    )
    (net (code "60") (name "unconnected-(H$58-PadP$1)") (class "Default")
      (node (ref "H$58") (pin "P$1") (pinfunction "P$1_P$1") (pintype "bidirectional"))
    )
    (net (code "61") (name "unconnected-(H$59-PadP$1)") (class "Default")
      (node (ref "H$59") (pin "P$1") (pinfunction "P$1_P$1") (pintype "bidirectional"))
    )
    (net (code "62") (name "unconnected-(H$60-PadP$1)") (class "Default")
      (node (ref "H$60") (pin "P$1") (pinfunction "P$1_P$1") (pintype "bidirectional"))
    )
    (net (code "63") (name "unconnected-(H$61-PadP$1)") (class "Default")
      (node (ref "H$61") (pin "P$1") (pinfunction "P$1_P$1") (pintype "bidirectional"))
    )
    (net (code "64") (name "unconnected-(H$62-PadP$1)") (class "Default")
      (node (ref "H$62") (pin "P$1") (pinfunction "P$1_P$1") (pintype "bidirectional"))
    )
    (net (code "65") (name "unconnected-(H$63-PadP$1)") (class "Default")
      (node (ref "H$63") (pin "P$1") (pinfunction "P$1_P$1") (pintype "bidirectional"))
    )
    (net (code "66") (name "unconnected-(H$64-PadP$1)") (class "Default")
      (node (ref "H$64") (pin "P$1") (pinfunction "P$1_P$1") (pintype "bidirectional"))
    )
    (net (code "67") (name "unconnected-(H$65-PadP$1)") (class "Default")
      (node (ref "H$65") (pin "P$1") (pinfunction "P$1_P$1") (pintype "bidirectional"))
    )
    (net (code "68") (name "unconnected-(H$66-PadP$1)") (class "Default")
      (node (ref "H$66") (pin "P$1") (pinfunction "P$1_P$1") (pintype "bidirectional"))
    )
    (net (code "69") (name "unconnected-(H$67-PadP$1)") (class "Default")
      (node (ref "H$67") (pin "P$1") (pinfunction "P$1_P$1") (pintype "bidirectional"))
    )
    (net (code "70") (name "unconnected-(H$68-PadP$1)") (class "Default")
      (node (ref "H$68") (pin "P$1") (pinfunction "P$1_P$1") (pintype "bidirectional"))
    )
    (net (code "71") (name "unconnected-(H$69-PadP$1)") (class "Default")
      (node (ref "H$69") (pin "P$1") (pinfunction "P$1_P$1") (pintype "bidirectional"))
    )
    (net (code "72") (name "unconnected-(H$70-PadP$1)") (class "Default")
      (node (ref "H$70") (pin "P$1") (pinfunction "P$1_P$1") (pintype "bidirectional"))
    )
    (net (code "73") (name "unconnected-(H$71-PadP$1)") (class "Default")
      (node (ref "H$71") (pin "P$1") (pinfunction "P$1_P$1") (pintype "bidirectional"))
    )
    (net (code "74") (name "unconnected-(H$72-PadP$1)") (class "Default")
      (node (ref "H$72") (pin "P$1") (pinfunction "P$1_P$1") (pintype "bidirectional"))
    )
    (net (code "75") (name "unconnected-(H$73-PadP$1)") (class "Default")
      (node (ref "H$73") (pin "P$1") (pinfunction "P$1_P$1") (pintype "bidirectional"))
    )
    (net (code "76") (name "unconnected-(H$74-PadP$1)") (class "Default")
      (node (ref "H$74") (pin "P$1") (pinfunction "P$1_P$1") (pintype "bidirectional"))
    )
    (net (code "77") (name "unconnected-(H$75-PadP$1)") (class "Default")
      (node (ref "H$75") (pin "P$1") (pinfunction "P$1_P$1") (pintype "bidirectional"))
    )
    (net (code "78") (name "unconnected-(H$76-PadP$1)") (class "Default")
      (node (ref "H$76") (pin "P$1") (pinfunction "P$1_P$1") (pintype "bidirectional"))
    )
    (net (code "79") (name "unconnected-(H$77-PadP$1)") (class "Default")
      (node (ref "H$77") (pin "P$1") (pinfunction "P$1_P$1") (pintype "bidirectional"))
    )
    (net (code "80") (name "unconnected-(H$78-PadP$1)") (class "Default")
      (node (ref "H$78") (pin "P$1") (pinfunction "P$1_P$1") (pintype "bidirectional"))
    )
    (net (code "81") (name "unconnected-(H$79-PadP$1)") (class "Default")
      (node (ref "H$79") (pin "P$1") (pinfunction "P$1_P$1") (pintype "bidirectional"))
    )
    (net (code "82") (name "unconnected-(H$80-PadP$1)") (class "Default")
      (node (ref "H$80") (pin "P$1") (pinfunction "P$1_P$1") (pintype "bidirectional"))
    )
    (net (code "83") (name "unconnected-(H$81-PadP$1)") (class "Default")
      (node (ref "H$81") (pin "P$1") (pinfunction "P$1_P$1") (pintype "bidirectional"))
    )
    (net (code "84") (name "unconnected-(H$82-PadP$1)") (class "Default")
      (node (ref "H$82") (pin "P$1") (pinfunction "P$1_P$1") (pintype "bidirectional"))
    )
    (net (code "85") (name "unconnected-(H$83-PadP$1)") (class "Default")
      (node (ref "H$83") (pin "P$1") (pinfunction "P$1_P$1") (pintype "bidirectional"))
    )
    (net (code "86") (name "unconnected-(H$84-PadP$1)") (class "Default")
      (node (ref "H$84") (pin "P$1") (pinfunction "P$1_P$1") (pintype "bidirectional"))
    )
    (net (code "87") (name "unconnected-(H$85-PadP$1)") (class "Default")
      (node (ref "H$85") (pin "P$1") (pinfunction "P$1_P$1") (pintype "bidirectional"))
    )
    (net (code "88") (name "unconnected-(H$86-PadP$1)") (class "Default")
      (node (ref "H$86") (pin "P$1") (pinfunction "P$1_P$1") (pintype "bidirectional"))
    )
    (net (code "89") (name "unconnected-(H$87-PadP$1)") (class "Default")
      (node (ref "H$87") (pin "P$1") (pinfunction "P$1_P$1") (pintype "bidirectional"))
    )
    (net (code "90") (name "unconnected-(H$88-PadP$1)") (class "Default")
      (node (ref "H$88") (pin "P$1") (pinfunction "P$1_P$1") (pintype "bidirectional"))
    )
    (net (code "91") (name "unconnected-(H$89-PadP$1)") (class "Default")
      (node (ref "H$89") (pin "P$1") (pinfunction "P$1_P$1") (pintype "bidirectional"))
    )
    (net (code "92") (name "unconnected-(H$90-PadP$1)") (class "Default")
      (node (ref "H$90") (pin "P$1") (pinfunction "P$1_P$1") (pintype "bidirectional"))
    )
    (net (code "93") (name "unconnected-(H$91-PadP$1)") (class "Default")
      (node (ref "H$91") (pin "P$1") (pinfunction "P$1_P$1") (pintype "bidirectional"))
    )
    (net (code "94") (name "unconnected-(H$92-PadP$1)") (class "Default")
      (node (ref "H$92") (pin "P$1") (pinfunction "P$1_P$1") (pintype "bidirectional"))
    )
    (net (code "95") (name "unconnected-(H$93-PadP$1)") (class "Default")
      (node (ref "H$93") (pin "P$1") (pinfunction "P$1_P$1") (pintype "bidirectional"))
    )
    (net (code "96") (name "unconnected-(H$94-PadP$1)") (class "Default")
      (node (ref "H$94") (pin "P$1") (pinfunction "P$1_P$1") (pintype "bidirectional"))
    )
    (net (code "97") (name "unconnected-(H$95-PadP$1)") (class "Default")
      (node (ref "H$95") (pin "P$1") (pinfunction "P$1_P$1") (pintype "bidirectional"))
    )
    (net (code "98") (name "unconnected-(H$96-PadP$1)") (class "Default")
      (node (ref "H$96") (pin "P$1") (pinfunction "P$1_P$1") (pintype "bidirectional"))
    )
    (net (code "99") (name "unconnected-(H$97-PadP$1)") (class "Default")
      (node (ref "H$97") (pin "P$1") (pinfunction "P$1_P$1") (pintype "bidirectional"))
    )
    (net (code "100") (name "unconnected-(H$98-PadP$1)") (class "Default")
      (node (ref "H$98") (pin "P$1") (pinfunction "P$1_P$1") (pintype "bidirectional"))
    )
    (net (code "101") (name "unconnected-(H$99-PadP$1)") (class "Default")
      (node (ref "H$99") (pin "P$1") (pinfunction "P$1_P$1") (pintype "bidirectional"))
    )
    (net (code "102") (name "unconnected-(H$100-PadP$1)") (class "Default")
      (node (ref "H$100") (pin "P$1") (pinfunction "P$1_P$1") (pintype "bidirectional"))
    )
    (net (code "103") (name "unconnected-(H$101-PadP$1)") (class "Default")
      (node (ref "H$101") (pin "P$1") (pinfunction "P$1_P$1") (pintype "bidirectional"))
    )
    (net (code "104") (name "unconnected-(H$102-PadP$1)") (class "Default")
      (node (ref "H$102") (pin "P$1") (pinfunction "P$1_P$1") (pintype "bidirectional"))
    )
    (net (code "105") (name "unconnected-(H$103-PadP$1)") (class "Default")
      (node (ref "H$103") (pin "P$1") (pinfunction "P$1_P$1") (pintype "bidirectional"))
    )
    (net (code "106") (name "unconnected-(H$104-PadP$1)") (class "Default")
      (node (ref "H$104") (pin "P$1") (pinfunction "P$1_P$1") (pintype "bidirectional"))
    )
    (net (code "107") (name "unconnected-(H$105-PadP$1)") (class "Default")
      (node (ref "H$105") (pin "P$1") (pinfunction "P$1_P$1") (pintype "bidirectional"))
    )
    (net (code "108") (name "unconnected-(H$106-PadP$1)") (class "Default")
      (node (ref "H$106") (pin "P$1") (pinfunction "P$1_P$1") (pintype "bidirectional"))
    )
    (net (code "109") (name "unconnected-(H$107-PadP$1)") (class "Default")
      (node (ref "H$107") (pin "P$1") (pinfunction "P$1_P$1") (pintype "bidirectional"))
    )
    (net (code "110") (name "unconnected-(H$108-PadP$1)") (class "Default")
      (node (ref "H$108") (pin "P$1") (pinfunction "P$1_P$1") (pintype "bidirectional"))
    )
    (net (code "111") (name "unconnected-(H$109-PadP$1)") (class "Default")
      (node (ref "H$109") (pin "P$1") (pinfunction "P$1_P$1") (pintype "bidirectional"))
    )
    (net (code "112") (name "unconnected-(H$110-PadP$1)") (class "Default")
      (node (ref "H$110") (pin "P$1") (pinfunction "P$1_P$1") (pintype "bidirectional"))
    )
    (net (code "113") (name "unconnected-(H$111-PadP$1)") (class "Default")
      (node (ref "H$111") (pin "P$1") (pinfunction "P$1_P$1") (pintype "bidirectional"))
    )
    (net (code "114") (name "unconnected-(H$112-PadP$1)") (class "Default")
      (node (ref "H$112") (pin "P$1") (pinfunction "P$1_P$1") (pintype "bidirectional"))
    )
    (net (code "115") (name "unconnected-(H$113-PadP$1)") (class "Default")
      (node (ref "H$113") (pin "P$1") (pinfunction "P$1_P$1") (pintype "bidirectional"))
    )
    (net (code "116") (name "unconnected-(H$114-PadP$1)") (class "Default")
      (node (ref "H$114") (pin "P$1") (pinfunction "P$1_P$1") (pintype "bidirectional"))
    )
    (net (code "117") (name "unconnected-(H$115-PadP$1)") (class "Default")
      (node (ref "H$115") (pin "P$1") (pinfunction "P$1_P$1") (pintype "bidirectional"))
    )
    (net (code "118") (name "unconnected-(H$116-PadP$1)") (class "Default")
      (node (ref "H$116") (pin "P$1") (pinfunction "P$1_P$1") (pintype "bidirectional"))
    )
    (net (code "119") (name "unconnected-(H$117-PadP$1)") (class "Default")
      (node (ref "H$117") (pin "P$1") (pinfunction "P$1_P$1") (pintype "bidirectional"))
    )
    (net (code "120") (name "unconnected-(H$118-PadP$1)") (class "Default")
      (node (ref "H$118") (pin "P$1") (pinfunction "P$1_P$1") (pintype "bidirectional"))
    )
    (net (code "121") (name "unconnected-(H$119-PadP$1)") (class "Default")
      (node (ref "H$119") (pin "P$1") (pinfunction "P$1_P$1") (pintype "bidirectional"))
    )
    (net (code "122") (name "unconnected-(H$120-PadP$1)") (class "Default")
      (node (ref "H$120") (pin "P$1") (pinfunction "P$1_P$1") (pintype "bidirectional"))
    )
    (net (code "123") (name "unconnected-(H$121-PadP$1)") (class "Default")
      (node (ref "H$121") (pin "P$1") (pinfunction "P$1_P$1") (pintype "bidirectional"))
    )
    (net (code "124") (name "unconnected-(H$122-PadP$1)") (class "Default")
      (node (ref "H$122") (pin "P$1") (pinfunction "P$1_P$1") (pintype "bidirectional"))
    )
    (net (code "125") (name "unconnected-(H$123-PadP$1)") (class "Default")
      (node (ref "H$123") (pin "P$1") (pinfunction "P$1_P$1") (pintype "bidirectional"))
    )
    (net (code "126") (name "unconnected-(H$124-PadP$1)") (class "Default")
      (node (ref "H$124") (pin "P$1") (pinfunction "P$1_P$1") (pintype "bidirectional"))
    )
    (net (code "127") (name "unconnected-(H$125-PadP$1)") (class "Default")
      (node (ref "H$125") (pin "P$1") (pinfunction "P$1_P$1") (pintype "bidirectional"))
    )
    (net (code "128") (name "unconnected-(H$126-PadP$1)") (class "Default")
      (node (ref "H$126") (pin "P$1") (pinfunction "P$1_P$1") (pintype "bidirectional"))
    )
    (net (code "129") (name "unconnected-(H$127-PadP$1)") (class "Default")
      (node (ref "H$127") (pin "P$1") (pinfunction "P$1_P$1") (pintype "bidirectional"))
    )
    (net (code "130") (name "unconnected-(U$1-CH0-PadP$0)") (class "Default")
      (node (ref "U$1") (pin "P$0") (pinfunction "CH0_P$0") (pintype "bidirectional"))
    )
    (net (code "131") (name "unconnected-(U$1-CH1-PadP$1)") (class "Default")
      (node (ref "U$1") (pin "P$1") (pinfunction "CH1_P$1") (pintype "bidirectional"))
    )
    (net (code "132") (name "unconnected-(U$1-CH2-PadP$2)") (class "Default")
      (node (ref "U$1") (pin "P$2") (pinfunction "CH2_P$2") (pintype "bidirectional"))
    )
    (net (code "133") (name "unconnected-(U$1-CH3-PadP$3)") (class "Default")
      (node (ref "U$1") (pin "P$3") (pinfunction "CH3_P$3") (pintype "bidirectional"))
    )
    (net (code "134") (name "unconnected-(U$1-CH4-PadP$4)") (class "Default")
      (node (ref "U$1") (pin "P$4") (pinfunction "CH4_P$4") (pintype "bidirectional"))
    )
    (net (code "135") (name "unconnected-(U$1-CH5-PadP$5)") (class "Default")
      (node (ref "U$1") (pin "P$5") (pinfunction "CH5_P$5") (pintype "bidirectional"))
    )
    (net (code "136") (name "unconnected-(U$1-CH6-PadP$6)") (class "Default")
      (node (ref "U$1") (pin "P$6") (pinfunction "CH6_P$6") (pintype "bidirectional"))
    )
    (net (code "137") (name "unconnected-(U$1-CH7-PadP$7)") (class "Default")
      (node (ref "U$1") (pin "P$7") (pinfunction "CH7_P$7") (pintype "bidirectional"))
    )
    (net (code "138") (name "unconnected-(U$1-CH8-PadP$8)") (class "Default")
      (node (ref "U$1") (pin "P$8") (pinfunction "CH8_P$8") (pintype "bidirectional"))
    )
    (net (code "139") (name "unconnected-(U$1-CH9-PadP$9)") (class "Default")
      (node (ref "U$1") (pin "P$9") (pinfunction "CH9_P$9") (pintype "bidirectional"))
    )
    (net (code "140") (name "unconnected-(U$1-CH10-PadP$10)") (class "Default")
      (node (ref "U$1") (pin "P$10") (pinfunction "CH10_P$10") (pintype "bidirectional"))
    )
    (net (code "141") (name "unconnected-(U$1-CH11-PadP$11)") (class "Default")
      (node (ref "U$1") (pin "P$11") (pinfunction "CH11_P$11") (pintype "bidirectional"))
    )
    (net (code "142") (name "unconnected-(U$1-CH12-PadP$12)") (class "Default")
      (node (ref "U$1") (pin "P$12") (pinfunction "CH12_P$12") (pintype "bidirectional"))
    )
    (net (code "143") (name "unconnected-(U$1-CH13-PadP$13)") (class "Default")
      (node (ref "U$1") (pin "P$13") (pinfunction "CH13_P$13") (pintype "bidirectional"))
    )
    (net (code "144") (name "unconnected-(U$1-CH14-PadP$14)") (class "Default")
      (node (ref "U$1") (pin "P$14") (pinfunction "CH14_P$14") (pintype "bidirectional"))
    )
    (net (code "145") (name "unconnected-(U$1-CH15-PadP$15)") (class "Default")
      (node (ref "U$1") (pin "P$15") (pinfunction "CH15_P$15") (pintype "bidirectional"))
    )
    (net (code "146") (name "unconnected-(U$1-CH16-PadP$16)") (class "Default")
      (node (ref "U$1") (pin "P$16") (pinfunction "CH16_P$16") (pintype "bidirectional"))
    )
    (net (code "147") (name "unconnected-(U$1-CH17-PadP$17)") (class "Default")
      (node (ref "U$1") (pin "P$17") (pinfunction "CH17_P$17") (pintype "bidirectional"))
    )
    (net (code "148") (name "unconnected-(U$1-CH18-PadP$18)") (class "Default")
      (node (ref "U$1") (pin "P$18") (pinfunction "CH18_P$18") (pintype "bidirectional"))
    )
    (net (code "149") (name "unconnected-(U$1-CH19-PadP$19)") (class "Default")
      (node (ref "U$1") (pin "P$19") (pinfunction "CH19_P$19") (pintype "bidirectional"))
    )
    (net (code "150") (name "unconnected-(U$1-CH20-PadP$20)") (class "Default")
      (node (ref "U$1") (pin "P$20") (pinfunction "CH20_P$20") (pintype "bidirectional"))
    )
    (net (code "151") (name "unconnected-(U$1-CH21-PadP$21)") (class "Default")
      (node (ref "U$1") (pin "P$21") (pinfunction "CH21_P$21") (pintype "bidirectional"))
    )
    (net (code "152") (name "unconnected-(U$1-CH22-PadP$22)") (class "Default")
      (node (ref "U$1") (pin "P$22") (pinfunction "CH22_P$22") (pintype "bidirectional"))
    )
    (net (code "153") (name "unconnected-(U$1-CH23-PadP$23)") (class "Default")
      (node (ref "U$1") (pin "P$23") (pinfunction "CH23_P$23") (pintype "bidirectional"))
    )
    (net (code "154") (name "unconnected-(U$1-CH24-PadP$24)") (class "Default")
      (node (ref "U$1") (pin "P$24") (pinfunction "CH24_P$24") (pintype "bidirectional"))
    )
    (net (code "155") (name "unconnected-(U$1-CH25-PadP$25)") (class "Default")
      (node (ref "U$1") (pin "P$25") (pinfunction "CH25_P$25") (pintype "bidirectional"))
    )
    (net (code "156") (name "unconnected-(U$1-CH26-PadP$26)") (class "Default")
      (node (ref "U$1") (pin "P$26") (pinfunction "CH26_P$26") (pintype "bidirectional"))
    )
    (net (code "157") (name "unconnected-(U$1-CH27-PadP$27)") (class "Default")
      (node (ref "U$1") (pin "P$27") (pinfunction "CH27_P$27") (pintype "bidirectional"))
    )
    (net (code "158") (name "unconnected-(U$1-CH28-PadP$28)") (class "Default")
      (node (ref "U$1") (pin "P$28") (pinfunction "CH28_P$28") (pintype "bidirectional"))
    )
    (net (code "159") (name "unconnected-(U$1-CH29-PadP$29)") (class "Default")
      (node (ref "U$1") (pin "P$29") (pinfunction "CH29_P$29") (pintype "bidirectional"))
    )
    (net (code "160") (name "unconnected-(U$1-CH30-PadP$30)") (class "Default")
      (node (ref "U$1") (pin "P$30") (pinfunction "CH30_P$30") (pintype "bidirectional"))
    )
    (net (code "161") (name "unconnected-(U$1-CH31-PadP$31)") (class "Default")
      (node (ref "U$1") (pin "P$31") (pinfunction "CH31_P$31") (pintype "bidirectional"))
    )
    (net (code "162") (name "unconnected-(U$1-CH32-PadP$32)") (class "Default")
      (node (ref "U$1") (pin "P$32") (pinfunction "CH32_P$32") (pintype "bidirectional"))
    )
    (net (code "163") (name "unconnected-(U$1-CH33-PadP$33)") (class "Default")
      (node (ref "U$1") (pin "P$33") (pinfunction "CH33_P$33") (pintype "bidirectional"))
    )
    (net (code "164") (name "unconnected-(U$1-CH34-PadP$34)") (class "Default")
      (node (ref "U$1") (pin "P$34") (pinfunction "CH34_P$34") (pintype "bidirectional"))
    )
    (net (code "165") (name "unconnected-(U$1-CH35-PadP$35)") (class "Default")
      (node (ref "U$1") (pin "P$35") (pinfunction "CH35_P$35") (pintype "bidirectional"))
    )
    (net (code "166") (name "unconnected-(U$1-CH36-PadP$36)") (class "Default")
      (node (ref "U$1") (pin "P$36") (pinfunction "CH36_P$36") (pintype "bidirectional"))
    )
    (net (code "167") (name "unconnected-(U$1-CH37-PadP$37)") (class "Default")
      (node (ref "U$1") (pin "P$37") (pinfunction "CH37_P$37") (pintype "bidirectional"))
    )
    (net (code "168") (name "unconnected-(U$1-CH38-PadP$38)") (class "Default")
      (node (ref "U$1") (pin "P$38") (pinfunction "CH38_P$38") (pintype "bidirectional"))
    )
    (net (code "169") (name "unconnected-(U$1-CH39-PadP$39)") (class "Default")
      (node (ref "U$1") (pin "P$39") (pinfunction "CH39_P$39") (pintype "bidirectional"))
    )
    (net (code "170") (name "unconnected-(U$1-CH40-PadP$40)") (class "Default")
      (node (ref "U$1") (pin "P$40") (pinfunction "CH40_P$40") (pintype "bidirectional"))
    )
    (net (code "171") (name "unconnected-(U$1-CH41-PadP$41)") (class "Default")
      (node (ref "U$1") (pin "P$41") (pinfunction "CH41_P$41") (pintype "bidirectional"))
    )
    (net (code "172") (name "unconnected-(U$1-CH42-PadP$42)") (class "Default")
      (node (ref "U$1") (pin "P$42") (pinfunction "CH42_P$42") (pintype "bidirectional"))
    )
    (net (code "173") (name "unconnected-(U$1-CH43-PadP$43)") (class "Default")
      (node (ref "U$1") (pin "P$43") (pinfunction "CH43_P$43") (pintype "bidirectional"))
    )
    (net (code "174") (name "unconnected-(U$1-CH44-PadP$44)") (class "Default")
      (node (ref "U$1") (pin "P$44") (pinfunction "CH44_P$44") (pintype "bidirectional"))
    )
    (net (code "175") (name "unconnected-(U$1-CH45-PadP$45)") (class "Default")
      (node (ref "U$1") (pin "P$45") (pinfunction "CH45_P$45") (pintype "bidirectional"))
    )
    (net (code "176") (name "unconnected-(U$1-CH46-PadP$46)") (class "Default")
      (node (ref "U$1") (pin "P$46") (pinfunction "CH46_P$46") (pintype "bidirectional"))
    )
    (net (code "177") (name "unconnected-(U$1-CH47-PadP$47)") (class "Default")
      (node (ref "U$1") (pin "P$47") (pinfunction "CH47_P$47") (pintype "bidirectional"))
    )
    (net (code "178") (name "unconnected-(U$1-CH48-PadP$48)") (class "Default")
      (node (ref "U$1") (pin "P$48") (pinfunction "CH48_P$48") (pintype "bidirectional"))
    )
    (net (code "179") (name "unconnected-(U$1-CH49-PadP$49)") (class "Default")
      (node (ref "U$1") (pin "P$49") (pinfunction "CH49_P$49") (pintype "bidirectional"))
    )
    (net (code "180") (name "unconnected-(U$1-CH50-PadP$50)") (class "Default")
      (node (ref "U$1") (pin "P$50") (pinfunction "CH50_P$50") (pintype "bidirectional"))
    )
    (net (code "181") (name "unconnected-(U$1-CH51-PadP$51)") (class "Default")
      (node (ref "U$1") (pin "P$51") (pinfunction "CH51_P$51") (pintype "bidirectional"))
    )
    (net (code "182") (name "unconnected-(U$1-CH52-PadP$52)") (class "Default")
      (node (ref "U$1") (pin "P$52") (pinfunction "CH52_P$52") (pintype "bidirectional"))
    )
    (net (code "183") (name "unconnected-(U$1-CH53-PadP$53)") (class "Default")
      (node (ref "U$1") (pin "P$53") (pinfunction "CH53_P$53") (pintype "bidirectional"))
    )
    (net (code "184") (name "unconnected-(U$1-CH54-PadP$54)") (class "Default")
      (node (ref "U$1") (pin "P$54") (pinfunction "CH54_P$54") (pintype "bidirectional"))
    )
    (net (code "185") (name "unconnected-(U$1-CH55-PadP$55)") (class "Default")
      (node (ref "U$1") (pin "P$55") (pinfunction "CH55_P$55") (pintype "bidirectional"))
    )
    (net (code "186") (name "unconnected-(U$1-CH56-PadP$56)") (class "Default")
      (node (ref "U$1") (pin "P$56") (pinfunction "CH56_P$56") (pintype "bidirectional"))
    )
    (net (code "187") (name "unconnected-(U$1-CH57-PadP$57)") (class "Default")
      (node (ref "U$1") (pin "P$57") (pinfunction "CH57_P$57") (pintype "bidirectional"))
    )
    (net (code "188") (name "unconnected-(U$1-CH58-PadP$58)") (class "Default")
      (node (ref "U$1") (pin "P$58") (pinfunction "CH58_P$58") (pintype "bidirectional"))
    )
    (net (code "189") (name "unconnected-(U$1-CH59-PadP$59)") (class "Default")
      (node (ref "U$1") (pin "P$59") (pinfunction "CH59_P$59") (pintype "bidirectional"))
    )
    (net (code "190") (name "unconnected-(U$1-CH60-PadP$60)") (class "Default")
      (node (ref "U$1") (pin "P$60") (pinfunction "CH60_P$60") (pintype "bidirectional"))
    )
    (net (code "191") (name "unconnected-(U$1-CH61-PadP$61)") (class "Default")
      (node (ref "U$1") (pin "P$61") (pinfunction "CH61_P$61") (pintype "bidirectional"))
    )
    (net (code "192") (name "unconnected-(U$1-CH62-PadP$62)") (class "Default")
      (node (ref "U$1") (pin "P$62") (pinfunction "CH62_P$62") (pintype "bidirectional"))
    )
    (net (code "193") (name "unconnected-(U$1-CH63-PadP$63)") (class "Default")
      (node (ref "U$1") (pin "P$63") (pinfunction "CH63_P$63") (pintype "bidirectional"))
    )
    (net (code "194") (name "unconnected-(U$1-PadGND3)") (class "Default")
      (node (ref "U$1") (pin "GND3") (pinfunction "GND3_GND3") (pintype "bidirectional"))
    )
    (net (code "195") (name "unconnected-(U$1-PadGND4)") (class "Default")
      (node (ref "U$1") (pin "GND4") (pinfunction "GND4_GND4") (pintype "bidirectional"))
    )
    (net (code "196") (name "unconnected-(U$1-PadREF1)") (class "Default")
      (node (ref "U$1") (pin "REF1") (pinfunction "REF1_REF1") (pintype "bidirectional"))
    )
    (net (code "197") (name "unconnected-(U$1-PadREF2)") (class "Default")
      (node (ref "U$1") (pin "REF2") (pinfunction "REF2_REF2") (pintype "bidirectional"))
    )
    (net (code "198") (name "unconnected-(U$2-CH0-PadP$0)") (class "Default")
      (node (ref "U$2") (pin "P$0") (pinfunction "CH0_P$0") (pintype "bidirectional"))
    )
    (net (code "199") (name "unconnected-(U$2-CH1-PadP$1)") (class "Default")
      (node (ref "U$2") (pin "P$1") (pinfunction "CH1_P$1") (pintype "bidirectional"))
    )
    (net (code "200") (name "unconnected-(U$2-CH2-PadP$2)") (class "Default")
      (node (ref "U$2") (pin "P$2") (pinfunction "CH2_P$2") (pintype "bidirectional"))
    )
    (net (code "201") (name "unconnected-(U$2-CH3-PadP$3)") (class "Default")
      (node (ref "U$2") (pin "P$3") (pinfunction "CH3_P$3") (pintype "bidirectional"))
    )
    (net (code "202") (name "unconnected-(U$2-CH4-PadP$4)") (class "Default")
      (node (ref "U$2") (pin "P$4") (pinfunction "CH4_P$4") (pintype "bidirectional"))
    )
    (net (code "203") (name "unconnected-(U$2-CH5-PadP$5)") (class "Default")
      (node (ref "U$2") (pin "P$5") (pinfunction "CH5_P$5") (pintype "bidirectional"))
    )
    (net (code "204") (name "unconnected-(U$2-CH6-PadP$6)") (class "Default")
      (node (ref "U$2") (pin "P$6") (pinfunction "CH6_P$6") (pintype "bidirectional"))
    )
    (net (code "205") (name "unconnected-(U$2-CH7-PadP$7)") (class "Default")
      (node (ref "U$2") (pin "P$7") (pinfunction "CH7_P$7") (pintype "bidirectional"))
    )
    (net (code "206") (name "unconnected-(U$2-CH8-PadP$8)") (class "Default")
      (node (ref "U$2") (pin "P$8") (pinfunction "CH8_P$8") (pintype "bidirectional"))
    )
    (net (code "207") (name "unconnected-(U$2-CH9-PadP$9)") (class "Default")
      (node (ref "U$2") (pin "P$9") (pinfunction "CH9_P$9") (pintype "bidirectional"))
    )
    (net (code "208") (name "unconnected-(U$2-CH10-PadP$10)") (class "Default")
      (node (ref "U$2") (pin "P$10") (pinfunction "CH10_P$10") (pintype "bidirectional"))
    )
    (net (code "209") (name "unconnected-(U$2-CH11-PadP$11)") (class "Default")
      (node (ref "U$2") (pin "P$11") (pinfunction "CH11_P$11") (pintype "bidirectional"))
    )
    (net (code "210") (name "unconnected-(U$2-CH12-PadP$12)") (class "Default")
      (node (ref "U$2") (pin "P$12") (pinfunction "CH12_P$12") (pintype "bidirectional"))
    )
    (net (code "211") (name "unconnected-(U$2-CH13-PadP$13)") (class "Default")
      (node (ref "U$2") (pin "P$13") (pinfunction "CH13_P$13") (pintype "bidirectional"))
    )
    (net (code "212") (name "unconnected-(U$2-CH14-PadP$14)") (class "Default")
      (node (ref "U$2") (pin "P$14") (pinfunction "CH14_P$14") (pintype "bidirectional"))
    )
    (net (code "213") (name "unconnected-(U$2-CH15-PadP$15)") (class "Default")
      (node (ref "U$2") (pin "P$15") (pinfunction "CH15_P$15") (pintype "bidirectional"))
    )
    (net (code "214") (name "unconnected-(U$2-CH16-PadP$16)") (class "Default")
      (node (ref "U$2") (pin "P$16") (pinfunction "CH16_P$16") (pintype "bidirectional"))
    )
    (net (code "215") (name "unconnected-(U$2-CH17-PadP$17)") (class "Default")
      (node (ref "U$2") (pin "P$17") (pinfunction "CH17_P$17") (pintype "bidirectional"))
    )
    (net (code "216") (name "unconnected-(U$2-CH18-PadP$18)") (class "Default")
      (node (ref "U$2") (pin "P$18") (pinfunction "CH18_P$18") (pintype "bidirectional"))
    )
    (net (code "217") (name "unconnected-(U$2-CH19-PadP$19)") (class "Default")
      (node (ref "U$2") (pin "P$19") (pinfunction "CH19_P$19") (pintype "bidirectional"))
    )
    (net (code "218") (name "unconnected-(U$2-CH20-PadP$20)") (class "Default")
      (node (ref "U$2") (pin "P$20") (pinfunction "CH20_P$20") (pintype "bidirectional"))
    )
    (net (code "219") (name "unconnected-(U$2-CH21-PadP$21)") (class "Default")
      (node (ref "U$2") (pin "P$21") (pinfunction "CH21_P$21") (pintype "bidirectional"))
    )
    (net (code "220") (name "unconnected-(U$2-CH22-PadP$22)") (class "Default")
      (node (ref "U$2") (pin "P$22") (pinfunction "CH22_P$22") (pintype "bidirectional"))
    )
    (net (code "221") (name "unconnected-(U$2-CH23-PadP$23)") (class "Default")
      (node (ref "U$2") (pin "P$23") (pinfunction "CH23_P$23") (pintype "bidirectional"))
    )
    (net (code "222") (name "unconnected-(U$2-CH24-PadP$24)") (class "Default")
      (node (ref "U$2") (pin "P$24") (pinfunction "CH24_P$24") (pintype "bidirectional"))
    )
    (net (code "223") (name "unconnected-(U$2-CH25-PadP$25)") (class "Default")
      (node (ref "U$2") (pin "P$25") (pinfunction "CH25_P$25") (pintype "bidirectional"))
    )
    (net (code "224") (name "unconnected-(U$2-CH26-PadP$26)") (class "Default")
      (node (ref "U$2") (pin "P$26") (pinfunction "CH26_P$26") (pintype "bidirectional"))
    )
    (net (code "225") (name "unconnected-(U$2-CH27-PadP$27)") (class "Default")
      (node (ref "U$2") (pin "P$27") (pinfunction "CH27_P$27") (pintype "bidirectional"))
    )
    (net (code "226") (name "unconnected-(U$2-CH28-PadP$28)") (class "Default")
      (node (ref "U$2") (pin "P$28") (pinfunction "CH28_P$28") (pintype "bidirectional"))
    )
    (net (code "227") (name "unconnected-(U$2-CH29-PadP$29)") (class "Default")
      (node (ref "U$2") (pin "P$29") (pinfunction "CH29_P$29") (pintype "bidirectional"))
    )
    (net (code "228") (name "unconnected-(U$2-CH30-PadP$30)") (class "Default")
      (node (ref "U$2") (pin "P$30") (pinfunction "CH30_P$30") (pintype "bidirectional"))
    )
    (net (code "229") (name "unconnected-(U$2-CH31-PadP$31)") (class "Default")
      (node (ref "U$2") (pin "P$31") (pinfunction "CH31_P$31") (pintype "bidirectional"))
    )
    (net (code "230") (name "unconnected-(U$2-CH32-PadP$32)") (class "Default")
      (node (ref "U$2") (pin "P$32") (pinfunction "CH32_P$32") (pintype "bidirectional"))
    )
    (net (code "231") (name "unconnected-(U$2-CH33-PadP$33)") (class "Default")
      (node (ref "U$2") (pin "P$33") (pinfunction "CH33_P$33") (pintype "bidirectional"))
    )
    (net (code "232") (name "unconnected-(U$2-CH34-PadP$34)") (class "Default")
      (node (ref "U$2") (pin "P$34") (pinfunction "CH34_P$34") (pintype "bidirectional"))
    )
    (net (code "233") (name "unconnected-(U$2-CH35-PadP$35)") (class "Default")
      (node (ref "U$2") (pin "P$35") (pinfunction "CH35_P$35") (pintype "bidirectional"))
    )
    (net (code "234") (name "unconnected-(U$2-CH36-PadP$36)") (class "Default")
      (node (ref "U$2") (pin "P$36") (pinfunction "CH36_P$36") (pintype "bidirectional"))
    )
    (net (code "235") (name "unconnected-(U$2-CH37-PadP$37)") (class "Default")
      (node (ref "U$2") (pin "P$37") (pinfunction "CH37_P$37") (pintype "bidirectional"))
    )
    (net (code "236") (name "unconnected-(U$2-CH38-PadP$38)") (class "Default")
      (node (ref "U$2") (pin "P$38") (pinfunction "CH38_P$38") (pintype "bidirectional"))
    )
    (net (code "237") (name "unconnected-(U$2-CH39-PadP$39)") (class "Default")
      (node (ref "U$2") (pin "P$39") (pinfunction "CH39_P$39") (pintype "bidirectional"))
    )
    (net (code "238") (name "unconnected-(U$2-CH40-PadP$40)") (class "Default")
      (node (ref "U$2") (pin "P$40") (pinfunction "CH40_P$40") (pintype "bidirectional"))
    )
    (net (code "239") (name "unconnected-(U$2-CH41-PadP$41)") (class "Default")
      (node (ref "U$2") (pin "P$41") (pinfunction "CH41_P$41") (pintype "bidirectional"))
    )
    (net (code "240") (name "unconnected-(U$2-CH42-PadP$42)") (class "Default")
      (node (ref "U$2") (pin "P$42") (pinfunction "CH42_P$42") (pintype "bidirectional"))
    )
    (net (code "241") (name "unconnected-(U$2-CH43-PadP$43)") (class "Default")
      (node (ref "U$2") (pin "P$43") (pinfunction "CH43_P$43") (pintype "bidirectional"))
    )
    (net (code "242") (name "unconnected-(U$2-CH44-PadP$44)") (class "Default")
      (node (ref "U$2") (pin "P$44") (pinfunction "CH44_P$44") (pintype "bidirectional"))
    )
    (net (code "243") (name "unconnected-(U$2-CH45-PadP$45)") (class "Default")
      (node (ref "U$2") (pin "P$45") (pinfunction "CH45_P$45") (pintype "bidirectional"))
    )
    (net (code "244") (name "unconnected-(U$2-CH46-PadP$46)") (class "Default")
      (node (ref "U$2") (pin "P$46") (pinfunction "CH46_P$46") (pintype "bidirectional"))
    )
    (net (code "245") (name "unconnected-(U$2-CH47-PadP$47)") (class "Default")
      (node (ref "U$2") (pin "P$47") (pinfunction "CH47_P$47") (pintype "bidirectional"))
    )
    (net (code "246") (name "unconnected-(U$2-CH48-PadP$48)") (class "Default")
      (node (ref "U$2") (pin "P$48") (pinfunction "CH48_P$48") (pintype "bidirectional"))
    )
    (net (code "247") (name "unconnected-(U$2-CH49-PadP$49)") (class "Default")
      (node (ref "U$2") (pin "P$49") (pinfunction "CH49_P$49") (pintype "bidirectional"))
    )
    (net (code "248") (name "unconnected-(U$2-CH50-PadP$50)") (class "Default")
      (node (ref "U$2") (pin "P$50") (pinfunction "CH50_P$50") (pintype "bidirectional"))
    )
    (net (code "249") (name "unconnected-(U$2-CH51-PadP$51)") (class "Default")
      (node (ref "U$2") (pin "P$51") (pinfunction "CH51_P$51") (pintype "bidirectional"))
    )
    (net (code "250") (name "unconnected-(U$2-CH52-PadP$52)") (class "Default")
      (node (ref "U$2") (pin "P$52") (pinfunction "CH52_P$52") (pintype "bidirectional"))
    )
    (net (code "251") (name "unconnected-(U$2-CH53-PadP$53)") (class "Default")
      (node (ref "U$2") (pin "P$53") (pinfunction "CH53_P$53") (pintype "bidirectional"))
    )
    (net (code "252") (name "unconnected-(U$2-CH54-PadP$54)") (class "Default")
      (node (ref "U$2") (pin "P$54") (pinfunction "CH54_P$54") (pintype "bidirectional"))
    )
    (net (code "253") (name "unconnected-(U$2-CH55-PadP$55)") (class "Default")
      (node (ref "U$2") (pin "P$55") (pinfunction "CH55_P$55") (pintype "bidirectional"))
    )
    (net (code "254") (name "unconnected-(U$2-CH56-PadP$56)") (class "Default")
      (node (ref "U$2") (pin "P$56") (pinfunction "CH56_P$56") (pintype "bidirectional"))
    )
    (net (code "255") (name "unconnected-(U$2-CH57-PadP$57)") (class "Default")
      (node (ref "U$2") (pin "P$57") (pinfunction "CH57_P$57") (pintype "bidirectional"))
    )
    (net (code "256") (name "unconnected-(U$2-CH58-PadP$58)") (class "Default")
      (node (ref "U$2") (pin "P$58") (pinfunction "CH58_P$58") (pintype "bidirectional"))
    )
    (net (code "257") (name "unconnected-(U$2-CH59-PadP$59)") (class "Default")
      (node (ref "U$2") (pin "P$59") (pinfunction "CH59_P$59") (pintype "bidirectional"))
    )
    (net (code "258") (name "unconnected-(U$2-CH60-PadP$60)") (class "Default")
      (node (ref "U$2") (pin "P$60") (pinfunction "CH60_P$60") (pintype "bidirectional"))
    )
    (net (code "259") (name "unconnected-(U$2-CH61-PadP$61)") (class "Default")
      (node (ref "U$2") (pin "P$61") (pinfunction "CH61_P$61") (pintype "bidirectional"))
    )
    (net (code "260") (name "unconnected-(U$2-CH62-PadP$62)") (class "Default")
      (node (ref "U$2") (pin "P$62") (pinfunction "CH62_P$62") (pintype "bidirectional"))
    )
    (net (code "261") (name "unconnected-(U$2-CH63-PadP$63)") (class "Default")
      (node (ref "U$2") (pin "P$63") (pinfunction "CH63_P$63") (pintype "bidirectional"))
    )
    (net (code "262") (name "unconnected-(U$2-PadGND1)") (class "Default")
      (node (ref "U$2") (pin "GND1") (pinfunction "GND1_GND1") (pintype "bidirectional"))
    )
    (net (code "263") (name "unconnected-(U$2-PadGND2)") (class "Default")
      (node (ref "U$2") (pin "GND2") (pinfunction "GND2_GND2") (pintype "bidirectional"))
    )
    (net (code "264") (name "unconnected-(U$2-PadREF1)") (class "Default")
      (node (ref "U$2") (pin "REF1") (pinfunction "REF1_REF1") (pintype "bidirectional"))
    )
    (net (code "265") (name "unconnected-(U$2-PadREF2)") (class "Default")
      (node (ref "U$2") (pin "REF2") (pinfunction "REF2_REF2") (pintype "bidirectional"))
    )
  )
)
